# M222X.net
KiCad netlist of a schematic drawn in EAGLE
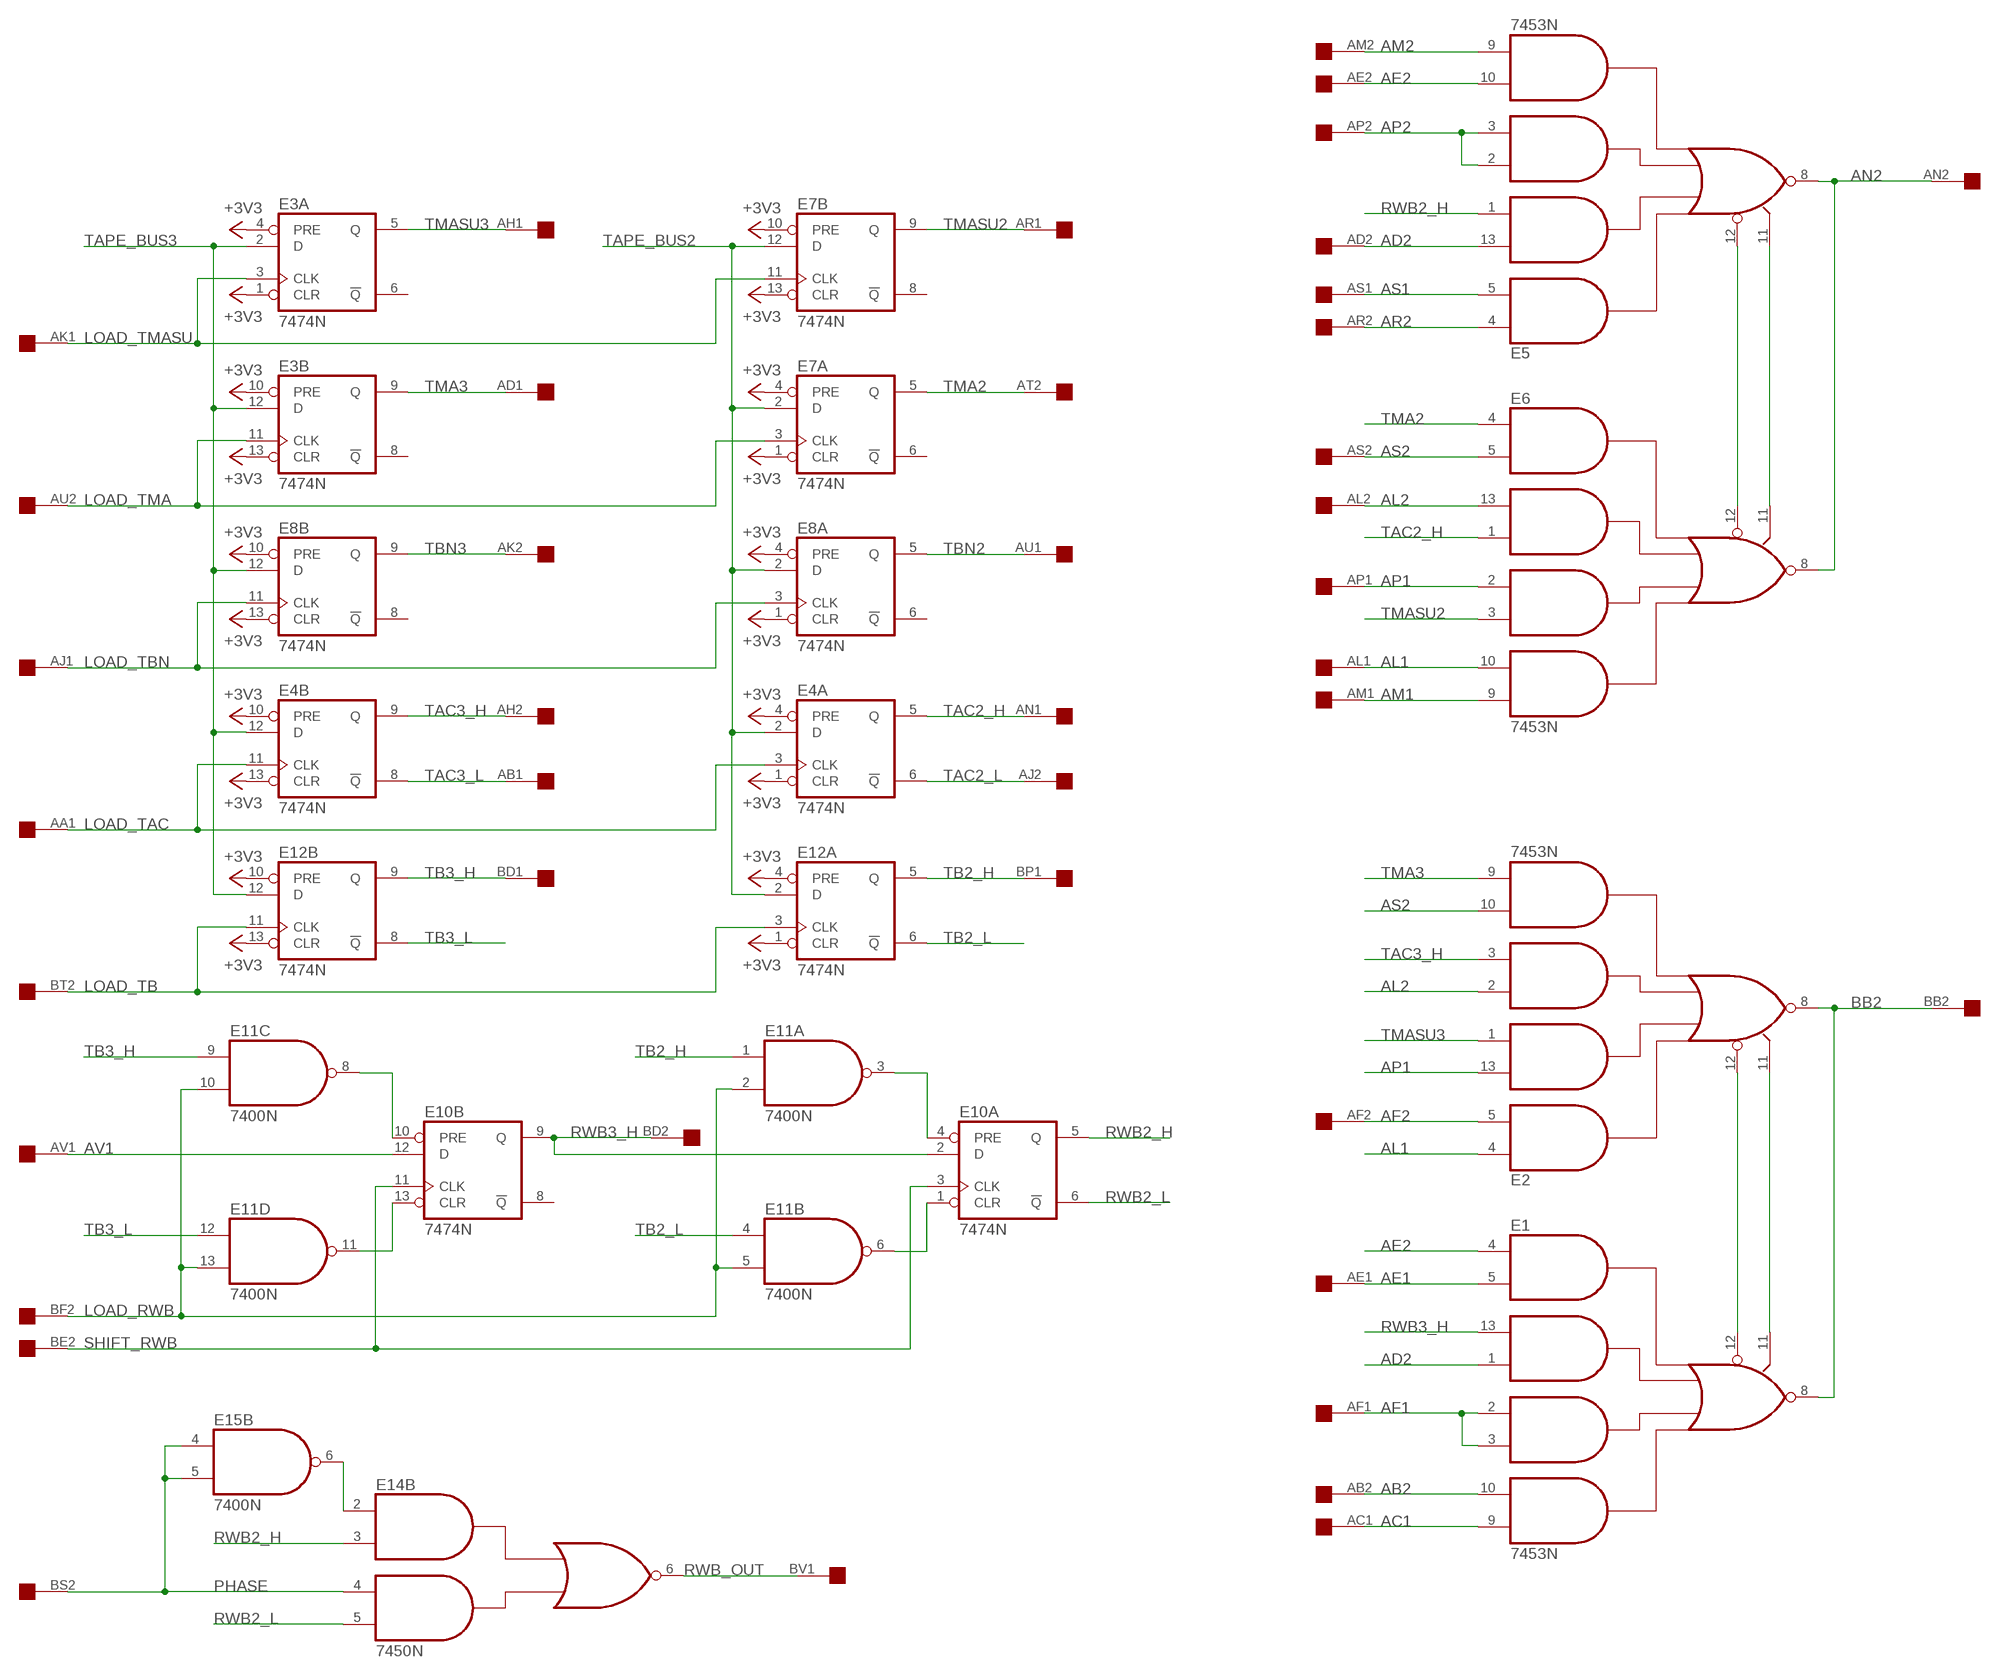
[diagram p0: schematic, sheet 1, part 1 of 2]
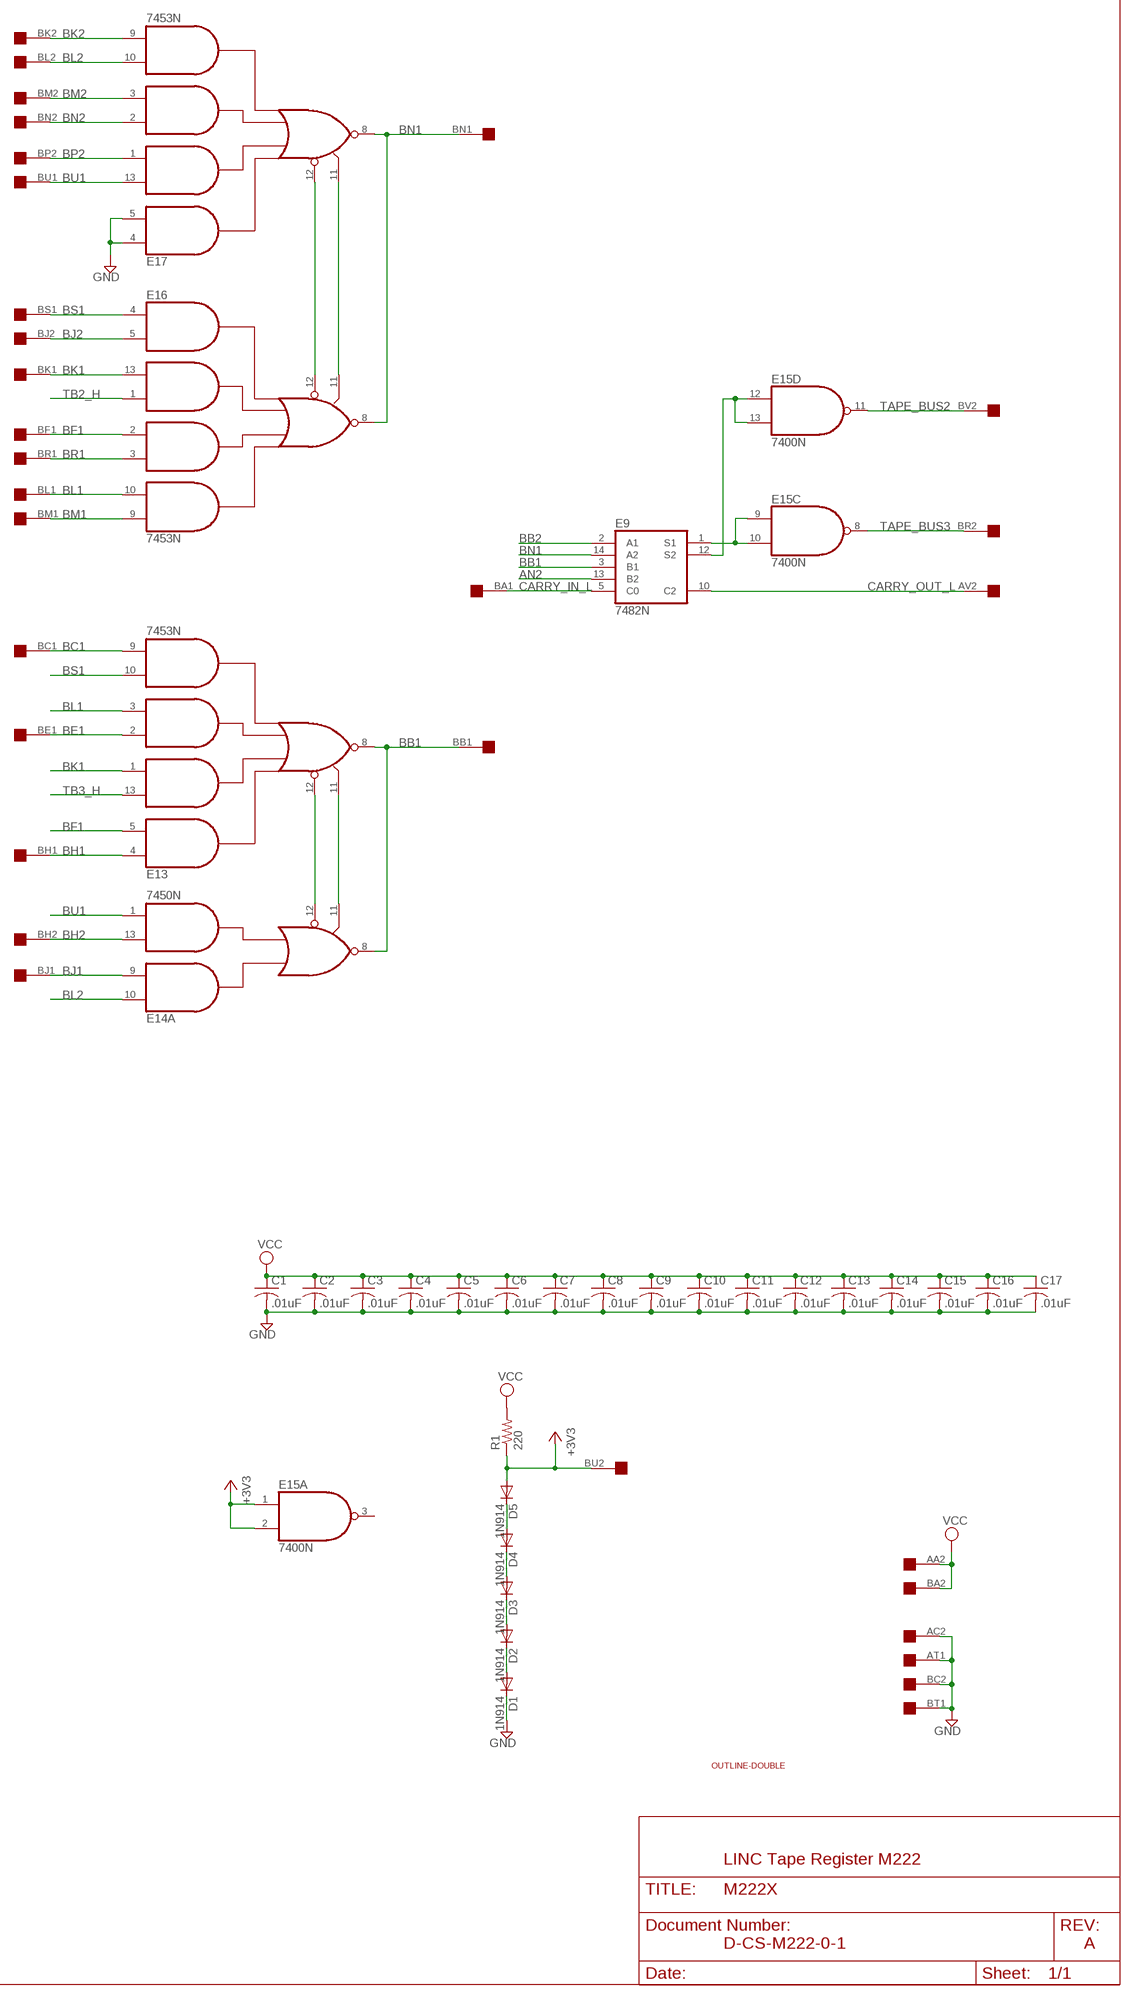
[diagram p1: schematic, sheet 1, part 2 of 2]

(export (version "E")
  (design (tool "Eeschema 10.0.6"))
  (components
    (comp (ref "C1")
      (value ".01uF")
      (footprint "eagle-import:C050-025X075")
      (libsource (lib "eagle-import") (part "C-US050-025X075"))
    )
    (comp (ref "C2")
      (value ".01uF")
      (footprint "eagle-import:C050-025X075")
      (libsource (lib "eagle-import") (part "C-US050-025X075"))
    )
    (comp (ref "C3")
      (value ".01uF")
      (footprint "eagle-import:C050-025X075")
      (libsource (lib "eagle-import") (part "C-US050-025X075"))
    )
    (comp (ref "C4")
      (value ".01uF")
      (footprint "eagle-import:C050-025X075")
      (libsource (lib "eagle-import") (part "C-US050-025X075"))
    )
    (comp (ref "C5")
      (value ".01uF")
      (footprint "eagle-import:C050-025X075")
      (libsource (lib "eagle-import") (part "C-US050-025X075"))
    )
    (comp (ref "C6")
      (value ".01uF")
      (footprint "eagle-import:C050-025X075")
      (libsource (lib "eagle-import") (part "C-US050-025X075"))
    )
    (comp (ref "C7")
      (value ".01uF")
      (footprint "eagle-import:C050-025X075")
      (libsource (lib "eagle-import") (part "C-US050-025X075"))
    )
    (comp (ref "C8")
      (value ".01uF")
      (footprint "eagle-import:C050-025X075")
      (libsource (lib "eagle-import") (part "C-US050-025X075"))
    )
    (comp (ref "C9")
      (value ".01uF")
      (footprint "eagle-import:C050-025X075")
      (libsource (lib "eagle-import") (part "C-US050-025X075"))
    )
    (comp (ref "C10")
      (value ".01uF")
      (footprint "eagle-import:C050-025X075")
      (libsource (lib "eagle-import") (part "C-US050-025X075"))
    )
    (comp (ref "C11")
      (value ".01uF")
      (footprint "eagle-import:C050-025X075")
      (libsource (lib "eagle-import") (part "C-US050-025X075"))
    )
    (comp (ref "C12")
      (value ".01uF")
      (footprint "eagle-import:C050-025X075")
      (libsource (lib "eagle-import") (part "C-US050-025X075"))
    )
    (comp (ref "C13")
      (value ".01uF")
      (footprint "eagle-import:C050-025X075")
      (libsource (lib "eagle-import") (part "C-US050-025X075"))
    )
    (comp (ref "C14")
      (value ".01uF")
      (footprint "eagle-import:C050-025X075")
      (libsource (lib "eagle-import") (part "C-US050-025X075"))
    )
    (comp (ref "C15")
      (value ".01uF")
      (footprint "eagle-import:C050-025X075")
      (libsource (lib "eagle-import") (part "C-US050-025X075"))
    )
    (comp (ref "C16")
      (value ".01uF")
      (footprint "eagle-import:C050-025X075")
      (libsource (lib "eagle-import") (part "C-US050-025X075"))
    )
    (comp (ref "C17")
      (value ".01uF")
      (footprint "eagle-import:C050-025X075")
      (libsource (lib "eagle-import") (part "C-US050-025X075"))
    )
    (comp (ref "D1")
      (value "1N914")
      (footprint "eagle-import:DO35-10")
      (libsource (lib "eagle-import") (part "1N4148DO35-10"))
    )
    (comp (ref "D2")
      (value "1N914")
      (footprint "eagle-import:DO35-10")
      (libsource (lib "eagle-import") (part "1N4148DO35-10"))
    )
    (comp (ref "D3")
      (value "1N914")
      (footprint "eagle-import:DO35-10")
      (libsource (lib "eagle-import") (part "1N4148DO35-10"))
    )
    (comp (ref "D4")
      (value "1N914")
      (footprint "eagle-import:DO35-10")
      (libsource (lib "eagle-import") (part "1N4148DO35-10"))
    )
    (comp (ref "D5")
      (value "1N914")
      (footprint "eagle-import:DO35-10")
      (libsource (lib "eagle-import") (part "1N4148DO35-10"))
    )
    (comp (ref "E1")
      (value "7453N")
      (footprint "eagle-import:DIL14")
      (libsource (lib "eagle-import") (part "7453N"))
    )
    (comp (ref "E2")
      (value "7453N")
      (footprint "eagle-import:DIL14")
      (libsource (lib "eagle-import") (part "7453N"))
    )
    (comp (ref "E3")
      (value "7474N")
      (footprint "eagle-import:DIL14")
      (libsource (lib "eagle-import") (part "7474NS"))
    )
    (comp (ref "E4")
      (value "7474N")
      (footprint "eagle-import:DIL14")
      (libsource (lib "eagle-import") (part "7474NS"))
    )
    (comp (ref "E5")
      (value "7453N")
      (footprint "eagle-import:DIL14")
      (libsource (lib "eagle-import") (part "7453N"))
    )
    (comp (ref "E6")
      (value "7453N")
      (footprint "eagle-import:DIL14")
      (libsource (lib "eagle-import") (part "7453N"))
    )
    (comp (ref "E7")
      (value "7474N")
      (footprint "eagle-import:DIL14")
      (libsource (lib "eagle-import") (part "7474NS"))
    )
    (comp (ref "E8")
      (value "7474N")
      (footprint "eagle-import:DIL14")
      (libsource (lib "eagle-import") (part "7474NS"))
    )
    (comp (ref "E9")
      (value "7482N")
      (footprint "eagle-import:DIL14")
      (libsource (lib "eagle-import") (part "7482N"))
    )
    (comp (ref "E10")
      (value "7474N")
      (footprint "eagle-import:DIL14")
      (libsource (lib "eagle-import") (part "7474NS"))
    )
    (comp (ref "E11")
      (value "7400N")
      (footprint "eagle-import:DIL14")
      (libsource (lib "eagle-import") (part "7400N"))
    )
    (comp (ref "E12")
      (value "7474N")
      (footprint "eagle-import:DIL14")
      (libsource (lib "eagle-import") (part "7474NS"))
    )
    (comp (ref "E13")
      (value "7453N")
      (footprint "eagle-import:DIL14")
      (libsource (lib "eagle-import") (part "7453N"))
    )
    (comp (ref "E14")
      (value "7450N")
      (footprint "eagle-import:DIL14")
      (libsource (lib "eagle-import") (part "7450N"))
    )
    (comp (ref "E15")
      (value "7400N")
      (footprint "eagle-import:DIL14")
      (libsource (lib "eagle-import") (part "7400N"))
    )
    (comp (ref "E16")
      (value "7453N")
      (footprint "eagle-import:DIL14")
      (libsource (lib "eagle-import") (part "7453N"))
    )
    (comp (ref "E17")
      (value "7453N")
      (footprint "eagle-import:DIL14")
      (libsource (lib "eagle-import") (part "7453N"))
    )
    (comp (ref "R1")
      (value "220")
      (footprint "eagle-import:0207_10")
      (libsource (lib "eagle-import") (part "R-US_0207/10"))
    )
    (comp (ref "U$1")
      (value "DOUBLE")
      (footprint "eagle-import:EDGE-CON4")
      (libsource (lib "eagle-import") (part "DOUBLE"))
    )
    (comp (ref "U$2")
      (value "OUTLINE-DOUBLE")
      (footprint "eagle-import:DOUBLE")
      (libsource (lib "eagle-import") (part "OUTLINE-DOUBLE"))
    )
  )
  (nets
    (net (code "1") (name "+3V3") (class "Default")
      (node (ref "D5") (pin "A") (pinfunction "A_A") (pintype "passive"))
      (node (ref "E12") (pin "1") (pinfunction "CLR_1") (pintype "input"))
      (node (ref "E12") (pin "10") (pinfunction "PRE_10") (pintype "input"))
      (node (ref "E12") (pin "13") (pinfunction "CLR_13") (pintype "input"))
      (node (ref "E12") (pin "4") (pinfunction "PRE_4") (pintype "input"))
      (node (ref "E15") (pin "1") (pinfunction "I0_1") (pintype "input"))
      (node (ref "E15") (pin "2") (pinfunction "I1_2") (pintype "input"))
      (node (ref "E3") (pin "1") (pinfunction "CLR_1") (pintype "input"))
      (node (ref "E3") (pin "10") (pinfunction "PRE_10") (pintype "input"))
      (node (ref "E3") (pin "13") (pinfunction "CLR_13") (pintype "input"))
      (node (ref "E3") (pin "4") (pinfunction "PRE_4") (pintype "input"))
      (node (ref "E4") (pin "1") (pinfunction "CLR_1") (pintype "input"))
      (node (ref "E4") (pin "10") (pinfunction "PRE_10") (pintype "input"))
      (node (ref "E4") (pin "13") (pinfunction "CLR_13") (pintype "input"))
      (node (ref "E4") (pin "4") (pinfunction "PRE_4") (pintype "input"))
      (node (ref "E7") (pin "1") (pinfunction "CLR_1") (pintype "input"))
      (node (ref "E7") (pin "10") (pinfunction "PRE_10") (pintype "input"))
      (node (ref "E7") (pin "13") (pinfunction "CLR_13") (pintype "input"))
      (node (ref "E7") (pin "4") (pinfunction "PRE_4") (pintype "input"))
      (node (ref "E8") (pin "1") (pinfunction "CLR_1") (pintype "input"))
      (node (ref "E8") (pin "10") (pinfunction "PRE_10") (pintype "input"))
      (node (ref "E8") (pin "13") (pinfunction "CLR_13") (pintype "input"))
      (node (ref "E8") (pin "4") (pinfunction "PRE_4") (pintype "input"))
      (node (ref "R1") (pin "1") (pinfunction "1_1") (pintype "passive"))
      (node (ref "U$1") (pin "BU2") (pinfunction "1_BU2") (pintype "bidirectional"))
    )
    (net (code "2") (name "/AB2") (class "Default")
      (node (ref "E1") (pin "10") (pinfunction "I7_10") (pintype "input"))
      (node (ref "U$1") (pin "AB2") (pinfunction "1_AB2") (pintype "bidirectional"))
    )
    (net (code "3") (name "/AC1") (class "Default")
      (node (ref "E1") (pin "9") (pinfunction "I8_9") (pintype "input"))
      (node (ref "U$1") (pin "AC1") (pinfunction "1_AC1") (pintype "bidirectional"))
    )
    (net (code "4") (name "/AD2") (class "Default")
      (node (ref "E1") (pin "1") (pinfunction "I4_1") (pintype "input"))
      (node (ref "E5") (pin "13") (pinfunction "I3_13") (pintype "input"))
      (node (ref "U$1") (pin "AD2") (pinfunction "1_AD2") (pintype "bidirectional"))
    )
    (net (code "5") (name "/AE1") (class "Default")
      (node (ref "E1") (pin "5") (pinfunction "I2_5") (pintype "input"))
      (node (ref "U$1") (pin "AE1") (pinfunction "1_AE1") (pintype "bidirectional"))
    )
    (net (code "6") (name "/AE2") (class "Default")
      (node (ref "E1") (pin "4") (pinfunction "I1_4") (pintype "input"))
      (node (ref "E5") (pin "10") (pinfunction "I7_10") (pintype "input"))
      (node (ref "U$1") (pin "AE2") (pinfunction "1_AE2") (pintype "bidirectional"))
    )
    (net (code "7") (name "/AF1") (class "Default")
      (node (ref "E1") (pin "2") (pinfunction "I5_2") (pintype "input"))
      (node (ref "E1") (pin "3") (pinfunction "I6_3") (pintype "input"))
      (node (ref "U$1") (pin "AF1") (pinfunction "1_AF1") (pintype "bidirectional"))
    )
    (net (code "8") (name "/AF2") (class "Default")
      (node (ref "E2") (pin "5") (pinfunction "I2_5") (pintype "input"))
      (node (ref "U$1") (pin "AF2") (pinfunction "1_AF2") (pintype "bidirectional"))
    )
    (net (code "9") (name "/AL1") (class "Default")
      (node (ref "E2") (pin "4") (pinfunction "I1_4") (pintype "input"))
      (node (ref "E6") (pin "10") (pinfunction "I7_10") (pintype "input"))
      (node (ref "U$1") (pin "AL1") (pinfunction "1_AL1") (pintype "bidirectional"))
    )
    (net (code "10") (name "/AL2") (class "Default")
      (node (ref "E2") (pin "2") (pinfunction "I5_2") (pintype "input"))
      (node (ref "E6") (pin "13") (pinfunction "I3_13") (pintype "input"))
      (node (ref "U$1") (pin "AL2") (pinfunction "1_AL2") (pintype "bidirectional"))
    )
    (net (code "11") (name "/AM1") (class "Default")
      (node (ref "E6") (pin "9") (pinfunction "I8_9") (pintype "input"))
      (node (ref "U$1") (pin "AM1") (pinfunction "1_AM1") (pintype "bidirectional"))
    )
    (net (code "12") (name "/AM2") (class "Default")
      (node (ref "E5") (pin "9") (pinfunction "I8_9") (pintype "input"))
      (node (ref "U$1") (pin "AM2") (pinfunction "1_AM2") (pintype "bidirectional"))
    )
    (net (code "13") (name "/AN2") (class "Default")
      (node (ref "E5") (pin "8") (pinfunction "O_8") (pintype "output"))
      (node (ref "E6") (pin "8") (pinfunction "O_8") (pintype "output"))
      (node (ref "E9") (pin "13") (pinfunction "B2_13") (pintype "input"))
      (node (ref "U$1") (pin "AN2") (pinfunction "1_AN2") (pintype "bidirectional"))
    )
    (net (code "14") (name "/AP1") (class "Default")
      (node (ref "E2") (pin "13") (pinfunction "I3_13") (pintype "input"))
      (node (ref "E6") (pin "2") (pinfunction "I5_2") (pintype "input"))
      (node (ref "U$1") (pin "AP1") (pinfunction "1_AP1") (pintype "bidirectional"))
    )
    (net (code "15") (name "/AP2") (class "Default")
      (node (ref "E5") (pin "2") (pinfunction "I5_2") (pintype "input"))
      (node (ref "E5") (pin "3") (pinfunction "I6_3") (pintype "input"))
      (node (ref "U$1") (pin "AP2") (pinfunction "1_AP2") (pintype "bidirectional"))
    )
    (net (code "16") (name "/AR2") (class "Default")
      (node (ref "E5") (pin "4") (pinfunction "I1_4") (pintype "input"))
      (node (ref "U$1") (pin "AR2") (pinfunction "1_AR2") (pintype "bidirectional"))
    )
    (net (code "17") (name "/AS1") (class "Default")
      (node (ref "E5") (pin "5") (pinfunction "I2_5") (pintype "input"))
      (node (ref "U$1") (pin "AS1") (pinfunction "1_AS1") (pintype "bidirectional"))
    )
    (net (code "18") (name "/AS2") (class "Default")
      (node (ref "E2") (pin "10") (pinfunction "I7_10") (pintype "input"))
      (node (ref "E6") (pin "5") (pinfunction "I2_5") (pintype "input"))
      (node (ref "U$1") (pin "AS2") (pinfunction "1_AS2") (pintype "bidirectional"))
    )
    (net (code "19") (name "/AV1") (class "Default")
      (node (ref "E10") (pin "12") (pinfunction "D_12") (pintype "input"))
      (node (ref "U$1") (pin "AV1") (pinfunction "1_AV1") (pintype "bidirectional"))
    )
    (net (code "20") (name "/BB1") (class "Default")
      (node (ref "E13") (pin "8") (pinfunction "O_8") (pintype "output"))
      (node (ref "E14") (pin "8") (pinfunction "O_8") (pintype "output"))
      (node (ref "E9") (pin "3") (pinfunction "B1_3") (pintype "input"))
      (node (ref "U$1") (pin "BB1") (pinfunction "1_BB1") (pintype "bidirectional"))
    )
    (net (code "21") (name "/BB2") (class "Default")
      (node (ref "E1") (pin "8") (pinfunction "O_8") (pintype "output"))
      (node (ref "E2") (pin "8") (pinfunction "O_8") (pintype "output"))
      (node (ref "E9") (pin "2") (pinfunction "A1_2") (pintype "input"))
      (node (ref "U$1") (pin "BB2") (pinfunction "1_BB2") (pintype "bidirectional"))
    )
    (net (code "22") (name "/BC1") (class "Default")
      (node (ref "E13") (pin "9") (pinfunction "I8_9") (pintype "input"))
      (node (ref "U$1") (pin "BC1") (pinfunction "1_BC1") (pintype "bidirectional"))
    )
    (net (code "23") (name "/BE1") (class "Default")
      (node (ref "E13") (pin "2") (pinfunction "I5_2") (pintype "input"))
      (node (ref "U$1") (pin "BE1") (pinfunction "1_BE1") (pintype "bidirectional"))
    )
    (net (code "24") (name "/BF1") (class "Default")
      (node (ref "E13") (pin "5") (pinfunction "I2_5") (pintype "input"))
      (node (ref "E16") (pin "2") (pinfunction "I5_2") (pintype "input"))
      (node (ref "U$1") (pin "BF1") (pinfunction "1_BF1") (pintype "bidirectional"))
    )
    (net (code "25") (name "/BH1") (class "Default")
      (node (ref "E13") (pin "4") (pinfunction "I1_4") (pintype "input"))
      (node (ref "U$1") (pin "BH1") (pinfunction "1_BH1") (pintype "bidirectional"))
    )
    (net (code "26") (name "/BH2") (class "Default")
      (node (ref "E14") (pin "13") (pinfunction "I3_13") (pintype "input"))
      (node (ref "U$1") (pin "BH2") (pinfunction "1_BH2") (pintype "bidirectional"))
    )
    (net (code "27") (name "/BJ1") (class "Default")
      (node (ref "E14") (pin "9") (pinfunction "I2_9") (pintype "input"))
      (node (ref "U$1") (pin "BJ1") (pinfunction "1_BJ1") (pintype "bidirectional"))
    )
    (net (code "28") (name "/BJ2") (class "Default")
      (node (ref "E16") (pin "5") (pinfunction "I2_5") (pintype "input"))
      (node (ref "U$1") (pin "BJ2") (pinfunction "1_BJ2") (pintype "bidirectional"))
    )
    (net (code "29") (name "/BK1") (class "Default")
      (node (ref "E13") (pin "1") (pinfunction "I4_1") (pintype "input"))
      (node (ref "E16") (pin "13") (pinfunction "I3_13") (pintype "input"))
      (node (ref "U$1") (pin "BK1") (pinfunction "1_BK1") (pintype "bidirectional"))
    )
    (net (code "30") (name "/BK2") (class "Default")
      (node (ref "E17") (pin "9") (pinfunction "I8_9") (pintype "input"))
      (node (ref "U$1") (pin "BK2") (pinfunction "1_BK2") (pintype "bidirectional"))
    )
    (net (code "31") (name "/BL1") (class "Default")
      (node (ref "E13") (pin "3") (pinfunction "I6_3") (pintype "input"))
      (node (ref "E16") (pin "10") (pinfunction "I7_10") (pintype "input"))
      (node (ref "U$1") (pin "BL1") (pinfunction "1_BL1") (pintype "bidirectional"))
    )
    (net (code "32") (name "/BL2") (class "Default")
      (node (ref "E14") (pin "10") (pinfunction "I1_10") (pintype "input"))
      (node (ref "E17") (pin "10") (pinfunction "I7_10") (pintype "input"))
      (node (ref "U$1") (pin "BL2") (pinfunction "1_BL2") (pintype "bidirectional"))
    )
    (net (code "33") (name "/BM1") (class "Default")
      (node (ref "E16") (pin "9") (pinfunction "I8_9") (pintype "input"))
      (node (ref "U$1") (pin "BM1") (pinfunction "1_BM1") (pintype "bidirectional"))
    )
    (net (code "34") (name "/BM2") (class "Default")
      (node (ref "E17") (pin "3") (pinfunction "I6_3") (pintype "input"))
      (node (ref "U$1") (pin "BM2") (pinfunction "1_BM2") (pintype "bidirectional"))
    )
    (net (code "35") (name "/BN1") (class "Default")
      (node (ref "E16") (pin "8") (pinfunction "O_8") (pintype "output"))
      (node (ref "E17") (pin "8") (pinfunction "O_8") (pintype "output"))
      (node (ref "E9") (pin "14") (pinfunction "A2_14") (pintype "input"))
      (node (ref "U$1") (pin "BN1") (pinfunction "1_BN1") (pintype "bidirectional"))
    )
    (net (code "36") (name "/BN2") (class "Default")
      (node (ref "E17") (pin "2") (pinfunction "I5_2") (pintype "input"))
      (node (ref "U$1") (pin "BN2") (pinfunction "1_BN2") (pintype "bidirectional"))
    )
    (net (code "37") (name "/BP2") (class "Default")
      (node (ref "E17") (pin "1") (pinfunction "I4_1") (pintype "input"))
      (node (ref "U$1") (pin "BP2") (pinfunction "1_BP2") (pintype "bidirectional"))
    )
    (net (code "38") (name "/BR1") (class "Default")
      (node (ref "E16") (pin "3") (pinfunction "I6_3") (pintype "input"))
      (node (ref "U$1") (pin "BR1") (pinfunction "1_BR1") (pintype "bidirectional"))
    )
    (net (code "39") (name "/BS1") (class "Default")
      (node (ref "E13") (pin "10") (pinfunction "I7_10") (pintype "input"))
      (node (ref "E16") (pin "4") (pinfunction "I1_4") (pintype "input"))
      (node (ref "U$1") (pin "BS1") (pinfunction "1_BS1") (pintype "bidirectional"))
    )
    (net (code "40") (name "/BU1") (class "Default")
      (node (ref "E14") (pin "1") (pinfunction "I4_1") (pintype "input"))
      (node (ref "E17") (pin "13") (pinfunction "I3_13") (pintype "input"))
      (node (ref "U$1") (pin "BU1") (pinfunction "1_BU1") (pintype "bidirectional"))
    )
    (net (code "41") (name "/CARRY_IN_L") (class "Default")
      (node (ref "E9") (pin "5") (pinfunction "C0_5") (pintype "input"))
      (node (ref "U$1") (pin "BA1") (pinfunction "1_BA1") (pintype "bidirectional"))
    )
    (net (code "42") (name "/CARRY_OUT_L") (class "Default")
      (node (ref "E9") (pin "10") (pinfunction "C2_10") (pintype "output"))
      (node (ref "U$1") (pin "AV2") (pinfunction "1_AV2") (pintype "bidirectional"))
    )
    (net (code "43") (name "/LOAD_RWB") (class "Default")
      (node (ref "E11") (pin "10") (pinfunction "I1_10") (pintype "input"))
      (node (ref "E11") (pin "13") (pinfunction "I1_13") (pintype "input"))
      (node (ref "E11") (pin "2") (pinfunction "I1_2") (pintype "input"))
      (node (ref "E11") (pin "5") (pinfunction "I1_5") (pintype "input"))
      (node (ref "U$1") (pin "BF2") (pinfunction "1_BF2") (pintype "bidirectional"))
    )
    (net (code "44") (name "/LOAD_TAC") (class "Default")
      (node (ref "E4") (pin "11") (pinfunction "CLK_11") (pintype "input"))
      (node (ref "E4") (pin "3") (pinfunction "CLK_3") (pintype "input"))
      (node (ref "U$1") (pin "AA1") (pinfunction "1_AA1") (pintype "bidirectional"))
    )
    (net (code "45") (name "/LOAD_TB") (class "Default")
      (node (ref "E12") (pin "11") (pinfunction "CLK_11") (pintype "input"))
      (node (ref "E12") (pin "3") (pinfunction "CLK_3") (pintype "input"))
      (node (ref "U$1") (pin "BT2") (pinfunction "1_BT2") (pintype "bidirectional"))
    )
    (net (code "46") (name "/LOAD_TBN") (class "Default")
      (node (ref "E8") (pin "11") (pinfunction "CLK_11") (pintype "input"))
      (node (ref "E8") (pin "3") (pinfunction "CLK_3") (pintype "input"))
      (node (ref "U$1") (pin "AJ1") (pinfunction "1_AJ1") (pintype "bidirectional"))
    )
    (net (code "47") (name "/LOAD_TMA") (class "Default")
      (node (ref "E3") (pin "11") (pinfunction "CLK_11") (pintype "input"))
      (node (ref "E7") (pin "3") (pinfunction "CLK_3") (pintype "input"))
      (node (ref "U$1") (pin "AU2") (pinfunction "1_AU2") (pintype "bidirectional"))
    )
    (net (code "48") (name "/LOAD_TMASU") (class "Default")
      (node (ref "E3") (pin "3") (pinfunction "CLK_3") (pintype "input"))
      (node (ref "E7") (pin "11") (pinfunction "CLK_11") (pintype "input"))
      (node (ref "U$1") (pin "AK1") (pinfunction "1_AK1") (pintype "bidirectional"))
    )
    (net (code "49") (name "/PHASE") (class "Default")
      (node (ref "E14") (pin "4") (pinfunction "I3_4") (pintype "input"))
      (node (ref "E15") (pin "4") (pinfunction "I0_4") (pintype "input"))
      (node (ref "E15") (pin "5") (pinfunction "I1_5") (pintype "input"))
      (node (ref "U$1") (pin "BS2") (pinfunction "1_BS2") (pintype "bidirectional"))
    )
    (net (code "50") (name "/RWB2_H") (class "Default")
      (node (ref "E10") (pin "5") (pinfunction "Q_5") (pintype "output"))
      (node (ref "E14") (pin "3") (pinfunction "I2_3") (pintype "input"))
      (node (ref "E5") (pin "1") (pinfunction "I4_1") (pintype "input"))
    )
    (net (code "51") (name "/RWB2_L") (class "Default")
      (node (ref "E10") (pin "6") (pinfunction "~{Q}_6") (pintype "output"))
      (node (ref "E14") (pin "5") (pinfunction "I4_5") (pintype "input"))
    )
    (net (code "52") (name "/RWB3_H") (class "Default")
      (node (ref "E1") (pin "13") (pinfunction "I3_13") (pintype "input"))
      (node (ref "E10") (pin "2") (pinfunction "D_2") (pintype "input"))
      (node (ref "E10") (pin "9") (pinfunction "Q_9") (pintype "output"))
      (node (ref "U$1") (pin "BD2") (pinfunction "1_BD2") (pintype "bidirectional"))
    )
    (net (code "53") (name "/RWB_OUT") (class "Default")
      (node (ref "E14") (pin "6") (pinfunction "O_6") (pintype "output"))
      (node (ref "U$1") (pin "BV1") (pinfunction "1_BV1") (pintype "bidirectional"))
    )
    (net (code "54") (name "/SHIFT_RWB") (class "Default")
      (node (ref "E10") (pin "11") (pinfunction "CLK_11") (pintype "input"))
      (node (ref "E10") (pin "3") (pinfunction "CLK_3") (pintype "input"))
      (node (ref "U$1") (pin "BE2") (pinfunction "1_BE2") (pintype "bidirectional"))
    )
    (net (code "55") (name "/TAC2_H") (class "Default")
      (node (ref "E4") (pin "5") (pinfunction "Q_5") (pintype "output"))
      (node (ref "E6") (pin "1") (pinfunction "I4_1") (pintype "input"))
      (node (ref "U$1") (pin "AN1") (pinfunction "1_AN1") (pintype "bidirectional"))
    )
    (net (code "56") (name "/TAC2_L") (class "Default")
      (node (ref "E4") (pin "6") (pinfunction "~{Q}_6") (pintype "output"))
      (node (ref "U$1") (pin "AJ2") (pinfunction "1_AJ2") (pintype "bidirectional"))
    )
    (net (code "57") (name "/TAC3_H") (class "Default")
      (node (ref "E2") (pin "3") (pinfunction "I6_3") (pintype "input"))
      (node (ref "E4") (pin "9") (pinfunction "Q_9") (pintype "output"))
      (node (ref "U$1") (pin "AH2") (pinfunction "1_AH2") (pintype "bidirectional"))
    )
    (net (code "58") (name "/TAC3_L") (class "Default")
      (node (ref "E4") (pin "8") (pinfunction "~{Q}_8") (pintype "output"))
      (node (ref "U$1") (pin "AB1") (pinfunction "1_AB1") (pintype "bidirectional"))
    )
    (net (code "59") (name "/TAPE_BUS2") (class "Default")
      (node (ref "E12") (pin "2") (pinfunction "D_2") (pintype "input"))
      (node (ref "E15") (pin "11") (pinfunction "O_11") (pintype "output"))
      (node (ref "E4") (pin "2") (pinfunction "D_2") (pintype "input"))
      (node (ref "E7") (pin "12") (pinfunction "D_12") (pintype "input"))
      (node (ref "E7") (pin "2") (pinfunction "D_2") (pintype "input"))
      (node (ref "E8") (pin "2") (pinfunction "D_2") (pintype "input"))
      (node (ref "U$1") (pin "BV2") (pinfunction "1_BV2") (pintype "bidirectional"))
    )
    (net (code "60") (name "/TAPE_BUS3") (class "Default")
      (node (ref "E12") (pin "12") (pinfunction "D_12") (pintype "input"))
      (node (ref "E15") (pin "8") (pinfunction "O_8") (pintype "output"))
      (node (ref "E3") (pin "12") (pinfunction "D_12") (pintype "input"))
      (node (ref "E3") (pin "2") (pinfunction "D_2") (pintype "input"))
      (node (ref "E4") (pin "12") (pinfunction "D_12") (pintype "input"))
      (node (ref "E8") (pin "12") (pinfunction "D_12") (pintype "input"))
      (node (ref "U$1") (pin "BR2") (pinfunction "1_BR2") (pintype "bidirectional"))
    )
    (net (code "61") (name "/TB2_H") (class "Default")
      (node (ref "E11") (pin "1") (pinfunction "I0_1") (pintype "input"))
      (node (ref "E12") (pin "5") (pinfunction "Q_5") (pintype "output"))
      (node (ref "E16") (pin "1") (pinfunction "I4_1") (pintype "input"))
      (node (ref "U$1") (pin "BP1") (pinfunction "1_BP1") (pintype "bidirectional"))
    )
    (net (code "62") (name "/TB2_L") (class "Default")
      (node (ref "E11") (pin "4") (pinfunction "I0_4") (pintype "input"))
      (node (ref "E12") (pin "6") (pinfunction "~{Q}_6") (pintype "output"))
    )
    (net (code "63") (name "/TB3_H") (class "Default")
      (node (ref "E11") (pin "9") (pinfunction "I0_9") (pintype "input"))
      (node (ref "E12") (pin "9") (pinfunction "Q_9") (pintype "output"))
      (node (ref "E13") (pin "13") (pinfunction "I3_13") (pintype "input"))
      (node (ref "U$1") (pin "BD1") (pinfunction "1_BD1") (pintype "bidirectional"))
    )
    (net (code "64") (name "/TB3_L") (class "Default")
      (node (ref "E11") (pin "12") (pinfunction "I0_12") (pintype "input"))
      (node (ref "E12") (pin "8") (pinfunction "~{Q}_8") (pintype "output"))
    )
    (net (code "65") (name "/TBN2") (class "Default")
      (node (ref "E8") (pin "5") (pinfunction "Q_5") (pintype "output"))
      (node (ref "U$1") (pin "AU1") (pinfunction "1_AU1") (pintype "bidirectional"))
    )
    (net (code "66") (name "/TBN3") (class "Default")
      (node (ref "E8") (pin "9") (pinfunction "Q_9") (pintype "output"))
      (node (ref "U$1") (pin "AK2") (pinfunction "1_AK2") (pintype "bidirectional"))
    )
    (net (code "67") (name "/TMA2") (class "Default")
      (node (ref "E6") (pin "4") (pinfunction "I1_4") (pintype "input"))
      (node (ref "E7") (pin "5") (pinfunction "Q_5") (pintype "output"))
      (node (ref "U$1") (pin "AT2") (pinfunction "1_AT2") (pintype "bidirectional"))
    )
    (net (code "68") (name "/TMA3") (class "Default")
      (node (ref "E2") (pin "9") (pinfunction "I8_9") (pintype "input"))
      (node (ref "E3") (pin "9") (pinfunction "Q_9") (pintype "output"))
      (node (ref "U$1") (pin "AD1") (pinfunction "1_AD1") (pintype "bidirectional"))
    )
    (net (code "69") (name "/TMASU2") (class "Default")
      (node (ref "E6") (pin "3") (pinfunction "I6_3") (pintype "input"))
      (node (ref "E7") (pin "9") (pinfunction "Q_9") (pintype "output"))
      (node (ref "U$1") (pin "AR1") (pinfunction "1_AR1") (pintype "bidirectional"))
    )
    (net (code "70") (name "/TMASU3") (class "Default")
      (node (ref "E2") (pin "1") (pinfunction "I4_1") (pintype "input"))
      (node (ref "E3") (pin "5") (pinfunction "Q_5") (pintype "output"))
      (node (ref "U$1") (pin "AH1") (pinfunction "1_AH1") (pintype "bidirectional"))
    )
    (net (code "71") (name "GND") (class "Default")
      (node (ref "C1") (pin "2") (pinfunction "2_2") (pintype "passive"))
      (node (ref "C10") (pin "2") (pinfunction "2_2") (pintype "passive"))
      (node (ref "C11") (pin "2") (pinfunction "2_2") (pintype "passive"))
      (node (ref "C12") (pin "2") (pinfunction "2_2") (pintype "passive"))
      (node (ref "C13") (pin "2") (pinfunction "2_2") (pintype "passive"))
      (node (ref "C14") (pin "2") (pinfunction "2_2") (pintype "passive"))
      (node (ref "C15") (pin "2") (pinfunction "2_2") (pintype "passive"))
      (node (ref "C16") (pin "2") (pinfunction "2_2") (pintype "passive"))
      (node (ref "C17") (pin "2") (pinfunction "2_2") (pintype "passive"))
      (node (ref "C2") (pin "2") (pinfunction "2_2") (pintype "passive"))
      (node (ref "C3") (pin "2") (pinfunction "2_2") (pintype "passive"))
      (node (ref "C4") (pin "2") (pinfunction "2_2") (pintype "passive"))
      (node (ref "C5") (pin "2") (pinfunction "2_2") (pintype "passive"))
      (node (ref "C6") (pin "2") (pinfunction "2_2") (pintype "passive"))
      (node (ref "C7") (pin "2") (pinfunction "2_2") (pintype "passive"))
      (node (ref "C8") (pin "2") (pinfunction "2_2") (pintype "passive"))
      (node (ref "C9") (pin "2") (pinfunction "2_2") (pintype "passive"))
      (node (ref "D1") (pin "C") (pinfunction "C_C") (pintype "passive"))
      (node (ref "E17") (pin "4") (pinfunction "I1_4") (pintype "input"))
      (node (ref "E17") (pin "5") (pinfunction "I2_5") (pintype "input"))
      (node (ref "U$1") (pin "AC2") (pinfunction "1_AC2") (pintype "bidirectional"))
      (node (ref "U$1") (pin "AT1") (pinfunction "1_AT1") (pintype "bidirectional"))
      (node (ref "U$1") (pin "BC2") (pinfunction "1_BC2") (pintype "bidirectional"))
      (node (ref "U$1") (pin "BT1") (pinfunction "1_BT1") (pintype "bidirectional"))
    )
    (net (code "72") (name "Net-(D1-PadA)") (class "Default")
      (node (ref "D1") (pin "A") (pinfunction "A_A") (pintype "passive"))
      (node (ref "D2") (pin "C") (pinfunction "C_C") (pintype "passive"))
    )
    (net (code "73") (name "Net-(D2-PadA)") (class "Default")
      (node (ref "D2") (pin "A") (pinfunction "A_A") (pintype "passive"))
      (node (ref "D3") (pin "C") (pinfunction "C_C") (pintype "passive"))
    )
    (net (code "74") (name "Net-(D3-PadA)") (class "Default")
      (node (ref "D3") (pin "A") (pinfunction "A_A") (pintype "passive"))
      (node (ref "D4") (pin "C") (pinfunction "C_C") (pintype "passive"))
    )
    (net (code "75") (name "Net-(D4-PadA)") (class "Default")
      (node (ref "D4") (pin "A") (pinfunction "A_A") (pintype "passive"))
      (node (ref "D5") (pin "C") (pinfunction "C_C") (pintype "passive"))
    )
    (net (code "76") (name "Net-(E1A-I9)") (class "Default")
      (node (ref "E1") (pin "12") (pinfunction "I9_12") (pintype "passive"))
      (node (ref "E2") (pin "12") (pinfunction "I9_12") (pintype "passive"))
    )
    (net (code "77") (name "Net-(E1A-I10)") (class "Default")
      (node (ref "E1") (pin "11") (pinfunction "I10_11") (pintype "passive"))
      (node (ref "E2") (pin "11") (pinfunction "I10_11") (pintype "passive"))
    )
    (net (code "78") (name "Net-(E5A-I9)") (class "Default")
      (node (ref "E5") (pin "12") (pinfunction "I9_12") (pintype "passive"))
      (node (ref "E6") (pin "12") (pinfunction "I9_12") (pintype "passive"))
    )
    (net (code "79") (name "Net-(E5A-I10)") (class "Default")
      (node (ref "E5") (pin "11") (pinfunction "I10_11") (pintype "passive"))
      (node (ref "E6") (pin "11") (pinfunction "I10_11") (pintype "passive"))
    )
    (net (code "80") (name "Net-(E10A-CLR)") (class "Default")
      (node (ref "E10") (pin "1") (pinfunction "CLR_1") (pintype "input"))
      (node (ref "E11") (pin "6") (pinfunction "O_6") (pintype "output"))
    )
    (net (code "81") (name "Net-(E10A-PRE)") (class "Default")
      (node (ref "E10") (pin "4") (pinfunction "PRE_4") (pintype "input"))
      (node (ref "E11") (pin "3") (pinfunction "O_3") (pintype "output"))
    )
    (net (code "82") (name "Net-(E10B-CLR)") (class "Default")
      (node (ref "E10") (pin "13") (pinfunction "CLR_13") (pintype "input"))
      (node (ref "E11") (pin "11") (pinfunction "O_11") (pintype "output"))
    )
    (net (code "83") (name "Net-(E10B-PRE)") (class "Default")
      (node (ref "E10") (pin "10") (pinfunction "PRE_10") (pintype "input"))
      (node (ref "E11") (pin "8") (pinfunction "O_8") (pintype "output"))
    )
    (net (code "84") (name "Net-(E13A-I9)") (class "Default")
      (node (ref "E13") (pin "12") (pinfunction "I9_12") (pintype "passive"))
      (node (ref "E14") (pin "12") (pinfunction "I5_12") (pintype "passive"))
    )
    (net (code "85") (name "Net-(E13A-I10)") (class "Default")
      (node (ref "E13") (pin "11") (pinfunction "I10_11") (pintype "passive"))
      (node (ref "E14") (pin "11") (pinfunction "I6_11") (pintype "passive"))
    )
    (net (code "86") (name "Net-(E14B-I1)") (class "Default")
      (node (ref "E14") (pin "2") (pinfunction "I1_2") (pintype "input"))
      (node (ref "E15") (pin "6") (pinfunction "O_6") (pintype "output"))
    )
    (net (code "87") (name "Net-(E15C-I0)") (class "Default")
      (node (ref "E15") (pin "10") (pinfunction "I1_10") (pintype "input"))
      (node (ref "E15") (pin "9") (pinfunction "I0_9") (pintype "input"))
      (node (ref "E9") (pin "1") (pinfunction "S1_1") (pintype "output"))
    )
    (net (code "88") (name "Net-(E15D-I0)") (class "Default")
      (node (ref "E15") (pin "12") (pinfunction "I0_12") (pintype "input"))
      (node (ref "E15") (pin "13") (pinfunction "I1_13") (pintype "input"))
      (node (ref "E9") (pin "12") (pinfunction "S2_12") (pintype "output"))
    )
    (net (code "89") (name "Net-(E16A-I9)") (class "Default")
      (node (ref "E16") (pin "12") (pinfunction "I9_12") (pintype "passive"))
      (node (ref "E17") (pin "12") (pinfunction "I9_12") (pintype "passive"))
    )
    (net (code "90") (name "Net-(E16A-I10)") (class "Default")
      (node (ref "E16") (pin "11") (pinfunction "I10_11") (pintype "passive"))
      (node (ref "E17") (pin "11") (pinfunction "I10_11") (pintype "passive"))
    )
    (net (code "91") (name "VCC") (class "Default")
      (node (ref "C1") (pin "1") (pinfunction "1_1") (pintype "passive"))
      (node (ref "C10") (pin "1") (pinfunction "1_1") (pintype "passive"))
      (node (ref "C11") (pin "1") (pinfunction "1_1") (pintype "passive"))
      (node (ref "C12") (pin "1") (pinfunction "1_1") (pintype "passive"))
      (node (ref "C13") (pin "1") (pinfunction "1_1") (pintype "passive"))
      (node (ref "C14") (pin "1") (pinfunction "1_1") (pintype "passive"))
      (node (ref "C15") (pin "1") (pinfunction "1_1") (pintype "passive"))
      (node (ref "C16") (pin "1") (pinfunction "1_1") (pintype "passive"))
      (node (ref "C17") (pin "1") (pinfunction "1_1") (pintype "passive"))
      (node (ref "C2") (pin "1") (pinfunction "1_1") (pintype "passive"))
      (node (ref "C3") (pin "1") (pinfunction "1_1") (pintype "passive"))
      (node (ref "C4") (pin "1") (pinfunction "1_1") (pintype "passive"))
      (node (ref "C5") (pin "1") (pinfunction "1_1") (pintype "passive"))
      (node (ref "C6") (pin "1") (pinfunction "1_1") (pintype "passive"))
      (node (ref "C7") (pin "1") (pinfunction "1_1") (pintype "passive"))
      (node (ref "C8") (pin "1") (pinfunction "1_1") (pintype "passive"))
      (node (ref "C9") (pin "1") (pinfunction "1_1") (pintype "passive"))
      (node (ref "R1") (pin "2") (pinfunction "2_2") (pintype "passive"))
      (node (ref "U$1") (pin "AA2") (pinfunction "1_AA2") (pintype "bidirectional"))
      (node (ref "U$1") (pin "BA2") (pinfunction "1_BA2") (pintype "bidirectional"))
    )
    (net (code "92") (name "unconnected-(E3A-~{Q}-Pad6)") (class "Default")
      (node (ref "E3") (pin "6") (pinfunction "~{Q}_6") (pintype "output"))
    )
    (net (code "93") (name "unconnected-(E3B-~{Q}-Pad8)") (class "Default")
      (node (ref "E3") (pin "8") (pinfunction "~{Q}_8") (pintype "output"))
    )
    (net (code "94") (name "unconnected-(E7A-~{Q}-Pad6)") (class "Default")
      (node (ref "E7") (pin "6") (pinfunction "~{Q}_6") (pintype "output"))
    )
    (net (code "95") (name "unconnected-(E7B-~{Q}-Pad8)") (class "Default")
      (node (ref "E7") (pin "8") (pinfunction "~{Q}_8") (pintype "output"))
    )
    (net (code "96") (name "unconnected-(E8A-~{Q}-Pad6)") (class "Default")
      (node (ref "E8") (pin "6") (pinfunction "~{Q}_6") (pintype "output"))
    )
    (net (code "97") (name "unconnected-(E8B-~{Q}-Pad8)") (class "Default")
      (node (ref "E8") (pin "8") (pinfunction "~{Q}_8") (pintype "output"))
    )
    (net (code "98") (name "unconnected-(E10B-~{Q}-Pad8)") (class "Default")
      (node (ref "E10") (pin "8") (pinfunction "~{Q}_8") (pintype "output"))
    )
    (net (code "99") (name "unconnected-(E15A-O-Pad3)") (class "Default")
      (node (ref "E15") (pin "3") (pinfunction "O_3") (pintype "output"))
    )
  )
)
